# Faceb.net
KiCad netlist of a schematic drawn in EAGLE
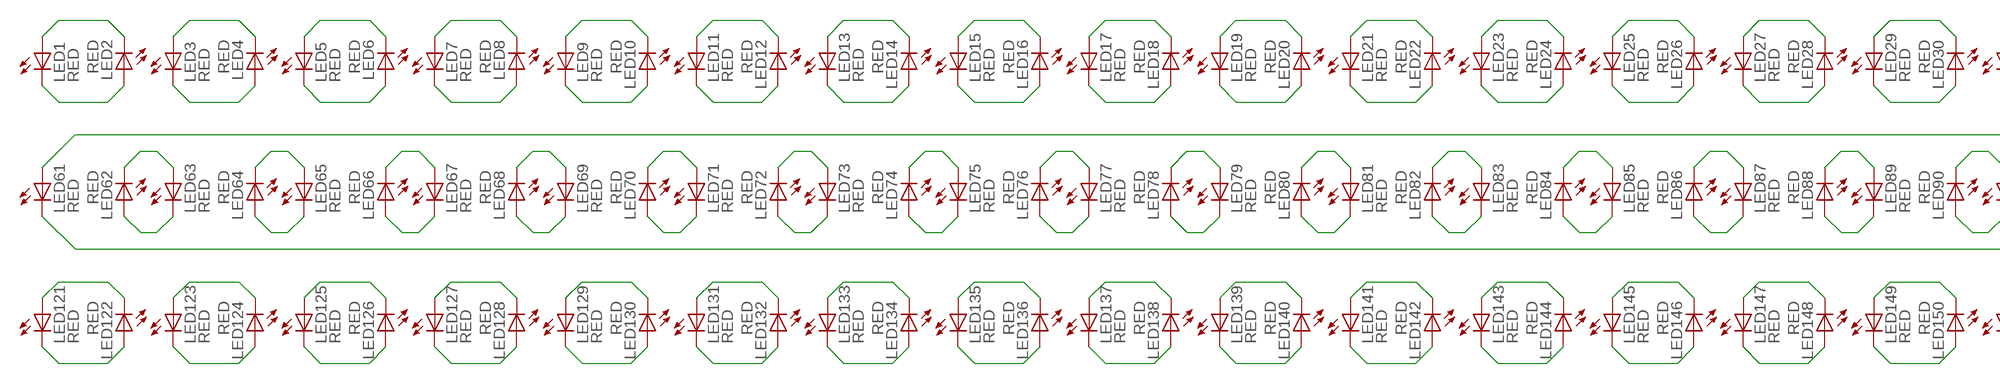
[diagram p0: schematic, sheet 1, part 1 of 2]
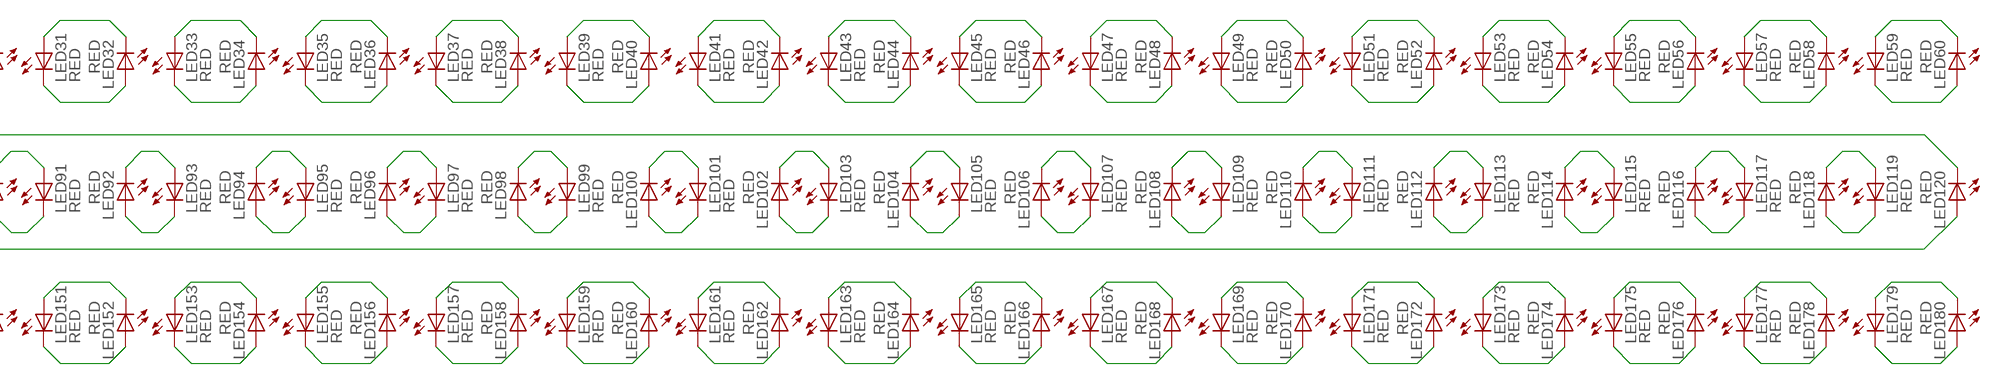
[diagram p1: schematic, sheet 1, part 2 of 2]

(export (version "E")
  (design (tool "Eeschema 10.0.6"))
  (components
    (comp (ref "LED1")
      (value "RED")
      (footprint "eagle-import:LED-0603")
      (libsource (lib "eagle-import") (part "LED0603"))
    )
    (comp (ref "LED2")
      (value "RED")
      (footprint "eagle-import:LED-0603")
      (libsource (lib "eagle-import") (part "LED0603"))
    )
    (comp (ref "LED3")
      (value "RED")
      (footprint "eagle-import:LED-0603")
      (libsource (lib "eagle-import") (part "LED0603"))
    )
    (comp (ref "LED4")
      (value "RED")
      (footprint "eagle-import:LED-0603")
      (libsource (lib "eagle-import") (part "LED0603"))
    )
    (comp (ref "LED5")
      (value "RED")
      (footprint "eagle-import:LED-0603")
      (libsource (lib "eagle-import") (part "LED0603"))
    )
    (comp (ref "LED6")
      (value "RED")
      (footprint "eagle-import:LED-0603")
      (libsource (lib "eagle-import") (part "LED0603"))
    )
    (comp (ref "LED7")
      (value "RED")
      (footprint "eagle-import:LED-0603")
      (libsource (lib "eagle-import") (part "LED0603"))
    )
    (comp (ref "LED8")
      (value "RED")
      (footprint "eagle-import:LED-0603")
      (libsource (lib "eagle-import") (part "LED0603"))
    )
    (comp (ref "LED9")
      (value "RED")
      (footprint "eagle-import:LED-0603")
      (libsource (lib "eagle-import") (part "LED0603"))
    )
    (comp (ref "LED10")
      (value "RED")
      (footprint "eagle-import:LED-0603")
      (libsource (lib "eagle-import") (part "LED0603"))
    )
    (comp (ref "LED11")
      (value "RED")
      (footprint "eagle-import:LED-0603")
      (libsource (lib "eagle-import") (part "LED0603"))
    )
    (comp (ref "LED12")
      (value "RED")
      (footprint "eagle-import:LED-0603")
      (libsource (lib "eagle-import") (part "LED0603"))
    )
    (comp (ref "LED13")
      (value "RED")
      (footprint "eagle-import:LED-0603")
      (libsource (lib "eagle-import") (part "LED0603"))
    )
    (comp (ref "LED14")
      (value "RED")
      (footprint "eagle-import:LED-0603")
      (libsource (lib "eagle-import") (part "LED0603"))
    )
    (comp (ref "LED15")
      (value "RED")
      (footprint "eagle-import:LED-0603")
      (libsource (lib "eagle-import") (part "LED0603"))
    )
    (comp (ref "LED16")
      (value "RED")
      (footprint "eagle-import:LED-0603")
      (libsource (lib "eagle-import") (part "LED0603"))
    )
    (comp (ref "LED17")
      (value "RED")
      (footprint "eagle-import:LED-0603")
      (libsource (lib "eagle-import") (part "LED0603"))
    )
    (comp (ref "LED18")
      (value "RED")
      (footprint "eagle-import:LED-0603")
      (libsource (lib "eagle-import") (part "LED0603"))
    )
    (comp (ref "LED19")
      (value "RED")
      (footprint "eagle-import:LED-0603")
      (libsource (lib "eagle-import") (part "LED0603"))
    )
    (comp (ref "LED20")
      (value "RED")
      (footprint "eagle-import:LED-0603")
      (libsource (lib "eagle-import") (part "LED0603"))
    )
    (comp (ref "LED21")
      (value "RED")
      (footprint "eagle-import:LED-0603")
      (libsource (lib "eagle-import") (part "LED0603"))
    )
    (comp (ref "LED22")
      (value "RED")
      (footprint "eagle-import:LED-0603")
      (libsource (lib "eagle-import") (part "LED0603"))
    )
    (comp (ref "LED23")
      (value "RED")
      (footprint "eagle-import:LED-0603")
      (libsource (lib "eagle-import") (part "LED0603"))
    )
    (comp (ref "LED24")
      (value "RED")
      (footprint "eagle-import:LED-0603")
      (libsource (lib "eagle-import") (part "LED0603"))
    )
    (comp (ref "LED25")
      (value "RED")
      (footprint "eagle-import:LED-0603")
      (libsource (lib "eagle-import") (part "LED0603"))
    )
    (comp (ref "LED26")
      (value "RED")
      (footprint "eagle-import:LED-0603")
      (libsource (lib "eagle-import") (part "LED0603"))
    )
    (comp (ref "LED27")
      (value "RED")
      (footprint "eagle-import:LED-0603")
      (libsource (lib "eagle-import") (part "LED0603"))
    )
    (comp (ref "LED28")
      (value "RED")
      (footprint "eagle-import:LED-0603")
      (libsource (lib "eagle-import") (part "LED0603"))
    )
    (comp (ref "LED29")
      (value "RED")
      (footprint "eagle-import:LED-0603")
      (libsource (lib "eagle-import") (part "LED0603"))
    )
    (comp (ref "LED30")
      (value "RED")
      (footprint "eagle-import:LED-0603")
      (libsource (lib "eagle-import") (part "LED0603"))
    )
    (comp (ref "LED31")
      (value "RED")
      (footprint "eagle-import:LED-0603")
      (libsource (lib "eagle-import") (part "LED0603"))
    )
    (comp (ref "LED32")
      (value "RED")
      (footprint "eagle-import:LED-0603")
      (libsource (lib "eagle-import") (part "LED0603"))
    )
    (comp (ref "LED33")
      (value "RED")
      (footprint "eagle-import:LED-0603")
      (libsource (lib "eagle-import") (part "LED0603"))
    )
    (comp (ref "LED34")
      (value "RED")
      (footprint "eagle-import:LED-0603")
      (libsource (lib "eagle-import") (part "LED0603"))
    )
    (comp (ref "LED35")
      (value "RED")
      (footprint "eagle-import:LED-0603")
      (libsource (lib "eagle-import") (part "LED0603"))
    )
    (comp (ref "LED36")
      (value "RED")
      (footprint "eagle-import:LED-0603")
      (libsource (lib "eagle-import") (part "LED0603"))
    )
    (comp (ref "LED37")
      (value "RED")
      (footprint "eagle-import:LED-0603")
      (libsource (lib "eagle-import") (part "LED0603"))
    )
    (comp (ref "LED38")
      (value "RED")
      (footprint "eagle-import:LED-0603")
      (libsource (lib "eagle-import") (part "LED0603"))
    )
    (comp (ref "LED39")
      (value "RED")
      (footprint "eagle-import:LED-0603")
      (libsource (lib "eagle-import") (part "LED0603"))
    )
    (comp (ref "LED40")
      (value "RED")
      (footprint "eagle-import:LED-0603")
      (libsource (lib "eagle-import") (part "LED0603"))
    )
    (comp (ref "LED41")
      (value "RED")
      (footprint "eagle-import:LED-0603")
      (libsource (lib "eagle-import") (part "LED0603"))
    )
    (comp (ref "LED42")
      (value "RED")
      (footprint "eagle-import:LED-0603")
      (libsource (lib "eagle-import") (part "LED0603"))
    )
    (comp (ref "LED43")
      (value "RED")
      (footprint "eagle-import:LED-0603")
      (libsource (lib "eagle-import") (part "LED0603"))
    )
    (comp (ref "LED44")
      (value "RED")
      (footprint "eagle-import:LED-0603")
      (libsource (lib "eagle-import") (part "LED0603"))
    )
    (comp (ref "LED45")
      (value "RED")
      (footprint "eagle-import:LED-0603")
      (libsource (lib "eagle-import") (part "LED0603"))
    )
    (comp (ref "LED46")
      (value "RED")
      (footprint "eagle-import:LED-0603")
      (libsource (lib "eagle-import") (part "LED0603"))
    )
    (comp (ref "LED47")
      (value "RED")
      (footprint "eagle-import:LED-0603")
      (libsource (lib "eagle-import") (part "LED0603"))
    )
    (comp (ref "LED48")
      (value "RED")
      (footprint "eagle-import:LED-0603")
      (libsource (lib "eagle-import") (part "LED0603"))
    )
    (comp (ref "LED49")
      (value "RED")
      (footprint "eagle-import:LED-0603")
      (libsource (lib "eagle-import") (part "LED0603"))
    )
    (comp (ref "LED50")
      (value "RED")
      (footprint "eagle-import:LED-0603")
      (libsource (lib "eagle-import") (part "LED0603"))
    )
    (comp (ref "LED51")
      (value "RED")
      (footprint "eagle-import:LED-0603")
      (libsource (lib "eagle-import") (part "LED0603"))
    )
    (comp (ref "LED52")
      (value "RED")
      (footprint "eagle-import:LED-0603")
      (libsource (lib "eagle-import") (part "LED0603"))
    )
    (comp (ref "LED53")
      (value "RED")
      (footprint "eagle-import:LED-0603")
      (libsource (lib "eagle-import") (part "LED0603"))
    )
    (comp (ref "LED54")
      (value "RED")
      (footprint "eagle-import:LED-0603")
      (libsource (lib "eagle-import") (part "LED0603"))
    )
    (comp (ref "LED55")
      (value "RED")
      (footprint "eagle-import:LED-0603")
      (libsource (lib "eagle-import") (part "LED0603"))
    )
    (comp (ref "LED56")
      (value "RED")
      (footprint "eagle-import:LED-0603")
      (libsource (lib "eagle-import") (part "LED0603"))
    )
    (comp (ref "LED57")
      (value "RED")
      (footprint "eagle-import:LED-0603")
      (libsource (lib "eagle-import") (part "LED0603"))
    )
    (comp (ref "LED58")
      (value "RED")
      (footprint "eagle-import:LED-0603")
      (libsource (lib "eagle-import") (part "LED0603"))
    )
    (comp (ref "LED59")
      (value "RED")
      (footprint "eagle-import:LED-0603")
      (libsource (lib "eagle-import") (part "LED0603"))
    )
    (comp (ref "LED60")
      (value "RED")
      (footprint "eagle-import:LED-0603")
      (libsource (lib "eagle-import") (part "LED0603"))
    )
    (comp (ref "LED61")
      (value "RED")
      (footprint "eagle-import:LED-0603")
      (libsource (lib "eagle-import") (part "LED0603"))
    )
    (comp (ref "LED62")
      (value "RED")
      (footprint "eagle-import:LED-0603")
      (libsource (lib "eagle-import") (part "LED0603"))
    )
    (comp (ref "LED63")
      (value "RED")
      (footprint "eagle-import:LED-0603")
      (libsource (lib "eagle-import") (part "LED0603"))
    )
    (comp (ref "LED64")
      (value "RED")
      (footprint "eagle-import:LED-0603")
      (libsource (lib "eagle-import") (part "LED0603"))
    )
    (comp (ref "LED65")
      (value "RED")
      (footprint "eagle-import:LED-0603")
      (libsource (lib "eagle-import") (part "LED0603"))
    )
    (comp (ref "LED66")
      (value "RED")
      (footprint "eagle-import:LED-0603")
      (libsource (lib "eagle-import") (part "LED0603"))
    )
    (comp (ref "LED67")
      (value "RED")
      (footprint "eagle-import:LED-0603")
      (libsource (lib "eagle-import") (part "LED0603"))
    )
    (comp (ref "LED68")
      (value "RED")
      (footprint "eagle-import:LED-0603")
      (libsource (lib "eagle-import") (part "LED0603"))
    )
    (comp (ref "LED69")
      (value "RED")
      (footprint "eagle-import:LED-0603")
      (libsource (lib "eagle-import") (part "LED0603"))
    )
    (comp (ref "LED70")
      (value "RED")
      (footprint "eagle-import:LED-0603")
      (libsource (lib "eagle-import") (part "LED0603"))
    )
    (comp (ref "LED71")
      (value "RED")
      (footprint "eagle-import:LED-0603")
      (libsource (lib "eagle-import") (part "LED0603"))
    )
    (comp (ref "LED72")
      (value "RED")
      (footprint "eagle-import:LED-0603")
      (libsource (lib "eagle-import") (part "LED0603"))
    )
    (comp (ref "LED73")
      (value "RED")
      (footprint "eagle-import:LED-0603")
      (libsource (lib "eagle-import") (part "LED0603"))
    )
    (comp (ref "LED74")
      (value "RED")
      (footprint "eagle-import:LED-0603")
      (libsource (lib "eagle-import") (part "LED0603"))
    )
    (comp (ref "LED75")
      (value "RED")
      (footprint "eagle-import:LED-0603")
      (libsource (lib "eagle-import") (part "LED0603"))
    )
    (comp (ref "LED76")
      (value "RED")
      (footprint "eagle-import:LED-0603")
      (libsource (lib "eagle-import") (part "LED0603"))
    )
    (comp (ref "LED77")
      (value "RED")
      (footprint "eagle-import:LED-0603")
      (libsource (lib "eagle-import") (part "LED0603"))
    )
    (comp (ref "LED78")
      (value "RED")
      (footprint "eagle-import:LED-0603")
      (libsource (lib "eagle-import") (part "LED0603"))
    )
    (comp (ref "LED79")
      (value "RED")
      (footprint "eagle-import:LED-0603")
      (libsource (lib "eagle-import") (part "LED0603"))
    )
    (comp (ref "LED80")
      (value "RED")
      (footprint "eagle-import:LED-0603")
      (libsource (lib "eagle-import") (part "LED0603"))
    )
    (comp (ref "LED81")
      (value "RED")
      (footprint "eagle-import:LED-0603")
      (libsource (lib "eagle-import") (part "LED0603"))
    )
    (comp (ref "LED82")
      (value "RED")
      (footprint "eagle-import:LED-0603")
      (libsource (lib "eagle-import") (part "LED0603"))
    )
    (comp (ref "LED83")
      (value "RED")
      (footprint "eagle-import:LED-0603")
      (libsource (lib "eagle-import") (part "LED0603"))
    )
    (comp (ref "LED84")
      (value "RED")
      (footprint "eagle-import:LED-0603")
      (libsource (lib "eagle-import") (part "LED0603"))
    )
    (comp (ref "LED85")
      (value "RED")
      (footprint "eagle-import:LED-0603")
      (libsource (lib "eagle-import") (part "LED0603"))
    )
    (comp (ref "LED86")
      (value "RED")
      (footprint "eagle-import:LED-0603")
      (libsource (lib "eagle-import") (part "LED0603"))
    )
    (comp (ref "LED87")
      (value "RED")
      (footprint "eagle-import:LED-0603")
      (libsource (lib "eagle-import") (part "LED0603"))
    )
    (comp (ref "LED88")
      (value "RED")
      (footprint "eagle-import:LED-0603")
      (libsource (lib "eagle-import") (part "LED0603"))
    )
    (comp (ref "LED89")
      (value "RED")
      (footprint "eagle-import:LED-0603")
      (libsource (lib "eagle-import") (part "LED0603"))
    )
    (comp (ref "LED90")
      (value "RED")
      (footprint "eagle-import:LED-0603")
      (libsource (lib "eagle-import") (part "LED0603"))
    )
    (comp (ref "LED91")
      (value "RED")
      (footprint "eagle-import:LED-0603")
      (libsource (lib "eagle-import") (part "LED0603"))
    )
    (comp (ref "LED92")
      (value "RED")
      (footprint "eagle-import:LED-0603")
      (libsource (lib "eagle-import") (part "LED0603"))
    )
    (comp (ref "LED93")
      (value "RED")
      (footprint "eagle-import:LED-0603")
      (libsource (lib "eagle-import") (part "LED0603"))
    )
    (comp (ref "LED94")
      (value "RED")
      (footprint "eagle-import:LED-0603")
      (libsource (lib "eagle-import") (part "LED0603"))
    )
    (comp (ref "LED95")
      (value "RED")
      (footprint "eagle-import:LED-0603")
      (libsource (lib "eagle-import") (part "LED0603"))
    )
    (comp (ref "LED96")
      (value "RED")
      (footprint "eagle-import:LED-0603")
      (libsource (lib "eagle-import") (part "LED0603"))
    )
    (comp (ref "LED97")
      (value "RED")
      (footprint "eagle-import:LED-0603")
      (libsource (lib "eagle-import") (part "LED0603"))
    )
    (comp (ref "LED98")
      (value "RED")
      (footprint "eagle-import:LED-0603")
      (libsource (lib "eagle-import") (part "LED0603"))
    )
    (comp (ref "LED99")
      (value "RED")
      (footprint "eagle-import:LED-0603")
      (libsource (lib "eagle-import") (part "LED0603"))
    )
    (comp (ref "LED100")
      (value "RED")
      (footprint "eagle-import:LED-0603")
      (libsource (lib "eagle-import") (part "LED0603"))
    )
    (comp (ref "LED101")
      (value "RED")
      (footprint "eagle-import:LED-0603")
      (libsource (lib "eagle-import") (part "LED0603"))
    )
    (comp (ref "LED102")
      (value "RED")
      (footprint "eagle-import:LED-0603")
      (libsource (lib "eagle-import") (part "LED0603"))
    )
    (comp (ref "LED103")
      (value "RED")
      (footprint "eagle-import:LED-0603")
      (libsource (lib "eagle-import") (part "LED0603"))
    )
    (comp (ref "LED104")
      (value "RED")
      (footprint "eagle-import:LED-0603")
      (libsource (lib "eagle-import") (part "LED0603"))
    )
    (comp (ref "LED105")
      (value "RED")
      (footprint "eagle-import:LED-0603")
      (libsource (lib "eagle-import") (part "LED0603"))
    )
    (comp (ref "LED106")
      (value "RED")
      (footprint "eagle-import:LED-0603")
      (libsource (lib "eagle-import") (part "LED0603"))
    )
    (comp (ref "LED107")
      (value "RED")
      (footprint "eagle-import:LED-0603")
      (libsource (lib "eagle-import") (part "LED0603"))
    )
    (comp (ref "LED108")
      (value "RED")
      (footprint "eagle-import:LED-0603")
      (libsource (lib "eagle-import") (part "LED0603"))
    )
    (comp (ref "LED109")
      (value "RED")
      (footprint "eagle-import:LED-0603")
      (libsource (lib "eagle-import") (part "LED0603"))
    )
    (comp (ref "LED110")
      (value "RED")
      (footprint "eagle-import:LED-0603")
      (libsource (lib "eagle-import") (part "LED0603"))
    )
    (comp (ref "LED111")
      (value "RED")
      (footprint "eagle-import:LED-0603")
      (libsource (lib "eagle-import") (part "LED0603"))
    )
    (comp (ref "LED112")
      (value "RED")
      (footprint "eagle-import:LED-0603")
      (libsource (lib "eagle-import") (part "LED0603"))
    )
    (comp (ref "LED113")
      (value "RED")
      (footprint "eagle-import:LED-0603")
      (libsource (lib "eagle-import") (part "LED0603"))
    )
    (comp (ref "LED114")
      (value "RED")
      (footprint "eagle-import:LED-0603")
      (libsource (lib "eagle-import") (part "LED0603"))
    )
    (comp (ref "LED115")
      (value "RED")
      (footprint "eagle-import:LED-0603")
      (libsource (lib "eagle-import") (part "LED0603"))
    )
    (comp (ref "LED116")
      (value "RED")
      (footprint "eagle-import:LED-0603")
      (libsource (lib "eagle-import") (part "LED0603"))
    )
    (comp (ref "LED117")
      (value "RED")
      (footprint "eagle-import:LED-0603")
      (libsource (lib "eagle-import") (part "LED0603"))
    )
    (comp (ref "LED118")
      (value "RED")
      (footprint "eagle-import:LED-0603")
      (libsource (lib "eagle-import") (part "LED0603"))
    )
    (comp (ref "LED119")
      (value "RED")
      (footprint "eagle-import:LED-0603")
      (libsource (lib "eagle-import") (part "LED0603"))
    )
    (comp (ref "LED120")
      (value "RED")
      (footprint "eagle-import:LED-0603")
      (libsource (lib "eagle-import") (part "LED0603"))
    )
    (comp (ref "LED121")
      (value "RED")
      (footprint "eagle-import:LED-0603")
      (libsource (lib "eagle-import") (part "LED0603"))
    )
    (comp (ref "LED122")
      (value "RED")
      (footprint "eagle-import:LED-0603")
      (libsource (lib "eagle-import") (part "LED0603"))
    )
    (comp (ref "LED123")
      (value "RED")
      (footprint "eagle-import:LED-0603")
      (libsource (lib "eagle-import") (part "LED0603"))
    )
    (comp (ref "LED124")
      (value "RED")
      (footprint "eagle-import:LED-0603")
      (libsource (lib "eagle-import") (part "LED0603"))
    )
    (comp (ref "LED125")
      (value "RED")
      (footprint "eagle-import:LED-0603")
      (libsource (lib "eagle-import") (part "LED0603"))
    )
    (comp (ref "LED126")
      (value "RED")
      (footprint "eagle-import:LED-0603")
      (libsource (lib "eagle-import") (part "LED0603"))
    )
    (comp (ref "LED127")
      (value "RED")
      (footprint "eagle-import:LED-0603")
      (libsource (lib "eagle-import") (part "LED0603"))
    )
    (comp (ref "LED128")
      (value "RED")
      (footprint "eagle-import:LED-0603")
      (libsource (lib "eagle-import") (part "LED0603"))
    )
    (comp (ref "LED129")
      (value "RED")
      (footprint "eagle-import:LED-0603")
      (libsource (lib "eagle-import") (part "LED0603"))
    )
    (comp (ref "LED130")
      (value "RED")
      (footprint "eagle-import:LED-0603")
      (libsource (lib "eagle-import") (part "LED0603"))
    )
    (comp (ref "LED131")
      (value "RED")
      (footprint "eagle-import:LED-0603")
      (libsource (lib "eagle-import") (part "LED0603"))
    )
    (comp (ref "LED132")
      (value "RED")
      (footprint "eagle-import:LED-0603")
      (libsource (lib "eagle-import") (part "LED0603"))
    )
    (comp (ref "LED133")
      (value "RED")
      (footprint "eagle-import:LED-0603")
      (libsource (lib "eagle-import") (part "LED0603"))
    )
    (comp (ref "LED134")
      (value "RED")
      (footprint "eagle-import:LED-0603")
      (libsource (lib "eagle-import") (part "LED0603"))
    )
    (comp (ref "LED135")
      (value "RED")
      (footprint "eagle-import:LED-0603")
      (libsource (lib "eagle-import") (part "LED0603"))
    )
    (comp (ref "LED136")
      (value "RED")
      (footprint "eagle-import:LED-0603")
      (libsource (lib "eagle-import") (part "LED0603"))
    )
    (comp (ref "LED137")
      (value "RED")
      (footprint "eagle-import:LED-0603")
      (libsource (lib "eagle-import") (part "LED0603"))
    )
    (comp (ref "LED138")
      (value "RED")
      (footprint "eagle-import:LED-0603")
      (libsource (lib "eagle-import") (part "LED0603"))
    )
    (comp (ref "LED139")
      (value "RED")
      (footprint "eagle-import:LED-0603")
      (libsource (lib "eagle-import") (part "LED0603"))
    )
    (comp (ref "LED140")
      (value "RED")
      (footprint "eagle-import:LED-0603")
      (libsource (lib "eagle-import") (part "LED0603"))
    )
    (comp (ref "LED141")
      (value "RED")
      (footprint "eagle-import:LED-0603")
      (libsource (lib "eagle-import") (part "LED0603"))
    )
    (comp (ref "LED142")
      (value "RED")
      (footprint "eagle-import:LED-0603")
      (libsource (lib "eagle-import") (part "LED0603"))
    )
    (comp (ref "LED143")
      (value "RED")
      (footprint "eagle-import:LED-0603")
      (libsource (lib "eagle-import") (part "LED0603"))
    )
    (comp (ref "LED144")
      (value "RED")
      (footprint "eagle-import:LED-0603")
      (libsource (lib "eagle-import") (part "LED0603"))
    )
    (comp (ref "LED145")
      (value "RED")
      (footprint "eagle-import:LED-0603")
      (libsource (lib "eagle-import") (part "LED0603"))
    )
    (comp (ref "LED146")
      (value "RED")
      (footprint "eagle-import:LED-0603")
      (libsource (lib "eagle-import") (part "LED0603"))
    )
    (comp (ref "LED147")
      (value "RED")
      (footprint "eagle-import:LED-0603")
      (libsource (lib "eagle-import") (part "LED0603"))
    )
    (comp (ref "LED148")
      (value "RED")
      (footprint "eagle-import:LED-0603")
      (libsource (lib "eagle-import") (part "LED0603"))
    )
    (comp (ref "LED149")
      (value "RED")
      (footprint "eagle-import:LED-0603")
      (libsource (lib "eagle-import") (part "LED0603"))
    )
    (comp (ref "LED150")
      (value "RED")
      (footprint "eagle-import:LED-0603")
      (libsource (lib "eagle-import") (part "LED0603"))
    )
    (comp (ref "LED151")
      (value "RED")
      (footprint "eagle-import:LED-0603")
      (libsource (lib "eagle-import") (part "LED0603"))
    )
    (comp (ref "LED152")
      (value "RED")
      (footprint "eagle-import:LED-0603")
      (libsource (lib "eagle-import") (part "LED0603"))
    )
    (comp (ref "LED153")
      (value "RED")
      (footprint "eagle-import:LED-0603")
      (libsource (lib "eagle-import") (part "LED0603"))
    )
    (comp (ref "LED154")
      (value "RED")
      (footprint "eagle-import:LED-0603")
      (libsource (lib "eagle-import") (part "LED0603"))
    )
    (comp (ref "LED155")
      (value "RED")
      (footprint "eagle-import:LED-0603")
      (libsource (lib "eagle-import") (part "LED0603"))
    )
    (comp (ref "LED156")
      (value "RED")
      (footprint "eagle-import:LED-0603")
      (libsource (lib "eagle-import") (part "LED0603"))
    )
    (comp (ref "LED157")
      (value "RED")
      (footprint "eagle-import:LED-0603")
      (libsource (lib "eagle-import") (part "LED0603"))
    )
    (comp (ref "LED158")
      (value "RED")
      (footprint "eagle-import:LED-0603")
      (libsource (lib "eagle-import") (part "LED0603"))
    )
    (comp (ref "LED159")
      (value "RED")
      (footprint "eagle-import:LED-0603")
      (libsource (lib "eagle-import") (part "LED0603"))
    )
    (comp (ref "LED160")
      (value "RED")
      (footprint "eagle-import:LED-0603")
      (libsource (lib "eagle-import") (part "LED0603"))
    )
    (comp (ref "LED161")
      (value "RED")
      (footprint "eagle-import:LED-0603")
      (libsource (lib "eagle-import") (part "LED0603"))
    )
    (comp (ref "LED162")
      (value "RED")
      (footprint "eagle-import:LED-0603")
      (libsource (lib "eagle-import") (part "LED0603"))
    )
    (comp (ref "LED163")
      (value "RED")
      (footprint "eagle-import:LED-0603")
      (libsource (lib "eagle-import") (part "LED0603"))
    )
    (comp (ref "LED164")
      (value "RED")
      (footprint "eagle-import:LED-0603")
      (libsource (lib "eagle-import") (part "LED0603"))
    )
    (comp (ref "LED165")
      (value "RED")
      (footprint "eagle-import:LED-0603")
      (libsource (lib "eagle-import") (part "LED0603"))
    )
    (comp (ref "LED166")
      (value "RED")
      (footprint "eagle-import:LED-0603")
      (libsource (lib "eagle-import") (part "LED0603"))
    )
    (comp (ref "LED167")
      (value "RED")
      (footprint "eagle-import:LED-0603")
      (libsource (lib "eagle-import") (part "LED0603"))
    )
    (comp (ref "LED168")
      (value "RED")
      (footprint "eagle-import:LED-0603")
      (libsource (lib "eagle-import") (part "LED0603"))
    )
    (comp (ref "LED169")
      (value "RED")
      (footprint "eagle-import:LED-0603")
      (libsource (lib "eagle-import") (part "LED0603"))
    )
    (comp (ref "LED170")
      (value "RED")
      (footprint "eagle-import:LED-0603")
      (libsource (lib "eagle-import") (part "LED0603"))
    )
    (comp (ref "LED171")
      (value "RED")
      (footprint "eagle-import:LED-0603")
      (libsource (lib "eagle-import") (part "LED0603"))
    )
    (comp (ref "LED172")
      (value "RED")
      (footprint "eagle-import:LED-0603")
      (libsource (lib "eagle-import") (part "LED0603"))
    )
    (comp (ref "LED173")
      (value "RED")
      (footprint "eagle-import:LED-0603")
      (libsource (lib "eagle-import") (part "LED0603"))
    )
    (comp (ref "LED174")
      (value "RED")
      (footprint "eagle-import:LED-0603")
      (libsource (lib "eagle-import") (part "LED0603"))
    )
    (comp (ref "LED175")
      (value "RED")
      (footprint "eagle-import:LED-0603")
      (libsource (lib "eagle-import") (part "LED0603"))
    )
    (comp (ref "LED176")
      (value "RED")
      (footprint "eagle-import:LED-0603")
      (libsource (lib "eagle-import") (part "LED0603"))
    )
    (comp (ref "LED177")
      (value "RED")
      (footprint "eagle-import:LED-0603")
      (libsource (lib "eagle-import") (part "LED0603"))
    )
    (comp (ref "LED178")
      (value "RED")
      (footprint "eagle-import:LED-0603")
      (libsource (lib "eagle-import") (part "LED0603"))
    )
    (comp (ref "LED179")
      (value "RED")
      (footprint "eagle-import:LED-0603")
      (libsource (lib "eagle-import") (part "LED0603"))
    )
    (comp (ref "LED180")
      (value "RED")
      (footprint "eagle-import:LED-0603")
      (libsource (lib "eagle-import") (part "LED0603"))
    )
  )
  (nets
    (net (code "1") (name "Net-(LED1-PadA)") (class "Default")
      (node (ref "LED1") (pin "A") (pinfunction "A_A") (pintype "passive"))
      (node (ref "LED2") (pin "C") (pinfunction "C_C") (pintype "passive"))
    )
    (net (code "2") (name "Net-(LED1-PadC)") (class "Default")
      (node (ref "LED1") (pin "C") (pinfunction "C_C") (pintype "passive"))
      (node (ref "LED2") (pin "A") (pinfunction "A_A") (pintype "passive"))
    )
    (net (code "3") (name "Net-(LED3-PadA)") (class "Default")
      (node (ref "LED3") (pin "A") (pinfunction "A_A") (pintype "passive"))
      (node (ref "LED4") (pin "C") (pinfunction "C_C") (pintype "passive"))
    )
    (net (code "4") (name "Net-(LED3-PadC)") (class "Default")
      (node (ref "LED3") (pin "C") (pinfunction "C_C") (pintype "passive"))
      (node (ref "LED4") (pin "A") (pinfunction "A_A") (pintype "passive"))
    )
    (net (code "5") (name "Net-(LED5-PadA)") (class "Default")
      (node (ref "LED5") (pin "A") (pinfunction "A_A") (pintype "passive"))
      (node (ref "LED6") (pin "C") (pinfunction "C_C") (pintype "passive"))
    )
    (net (code "6") (name "Net-(LED5-PadC)") (class "Default")
      (node (ref "LED5") (pin "C") (pinfunction "C_C") (pintype "passive"))
      (node (ref "LED6") (pin "A") (pinfunction "A_A") (pintype "passive"))
    )
    (net (code "7") (name "Net-(LED7-PadA)") (class "Default")
      (node (ref "LED7") (pin "A") (pinfunction "A_A") (pintype "passive"))
      (node (ref "LED8") (pin "C") (pinfunction "C_C") (pintype "passive"))
    )
    (net (code "8") (name "Net-(LED7-PadC)") (class "Default")
      (node (ref "LED7") (pin "C") (pinfunction "C_C") (pintype "passive"))
      (node (ref "LED8") (pin "A") (pinfunction "A_A") (pintype "passive"))
    )
    (net (code "9") (name "Net-(LED10-PadA)") (class "Default")
      (node (ref "LED10") (pin "A") (pinfunction "A_A") (pintype "passive"))
      (node (ref "LED9") (pin "C") (pinfunction "C_C") (pintype "passive"))
    )
    (net (code "10") (name "Net-(LED10-PadC)") (class "Default")
      (node (ref "LED10") (pin "C") (pinfunction "C_C") (pintype "passive"))
      (node (ref "LED9") (pin "A") (pinfunction "A_A") (pintype "passive"))
    )
    (net (code "11") (name "Net-(LED11-PadA)") (class "Default")
      (node (ref "LED11") (pin "A") (pinfunction "A_A") (pintype "passive"))
      (node (ref "LED12") (pin "C") (pinfunction "C_C") (pintype "passive"))
    )
    (net (code "12") (name "Net-(LED11-PadC)") (class "Default")
      (node (ref "LED11") (pin "C") (pinfunction "C_C") (pintype "passive"))
      (node (ref "LED12") (pin "A") (pinfunction "A_A") (pintype "passive"))
    )
    (net (code "13") (name "Net-(LED13-PadA)") (class "Default")
      (node (ref "LED13") (pin "A") (pinfunction "A_A") (pintype "passive"))
      (node (ref "LED14") (pin "C") (pinfunction "C_C") (pintype "passive"))
    )
    (net (code "14") (name "Net-(LED13-PadC)") (class "Default")
      (node (ref "LED13") (pin "C") (pinfunction "C_C") (pintype "passive"))
      (node (ref "LED14") (pin "A") (pinfunction "A_A") (pintype "passive"))
    )
    (net (code "15") (name "Net-(LED15-PadA)") (class "Default")
      (node (ref "LED15") (pin "A") (pinfunction "A_A") (pintype "passive"))
      (node (ref "LED16") (pin "C") (pinfunction "C_C") (pintype "passive"))
    )
    (net (code "16") (name "Net-(LED15-PadC)") (class "Default")
      (node (ref "LED15") (pin "C") (pinfunction "C_C") (pintype "passive"))
      (node (ref "LED16") (pin "A") (pinfunction "A_A") (pintype "passive"))
    )
    (net (code "17") (name "Net-(LED17-PadA)") (class "Default")
      (node (ref "LED17") (pin "A") (pinfunction "A_A") (pintype "passive"))
      (node (ref "LED18") (pin "C") (pinfunction "C_C") (pintype "passive"))
    )
    (net (code "18") (name "Net-(LED17-PadC)") (class "Default")
      (node (ref "LED17") (pin "C") (pinfunction "C_C") (pintype "passive"))
      (node (ref "LED18") (pin "A") (pinfunction "A_A") (pintype "passive"))
    )
    (net (code "19") (name "Net-(LED19-PadA)") (class "Default")
      (node (ref "LED19") (pin "A") (pinfunction "A_A") (pintype "passive"))
      (node (ref "LED20") (pin "C") (pinfunction "C_C") (pintype "passive"))
    )
    (net (code "20") (name "Net-(LED19-PadC)") (class "Default")
      (node (ref "LED19") (pin "C") (pinfunction "C_C") (pintype "passive"))
      (node (ref "LED20") (pin "A") (pinfunction "A_A") (pintype "passive"))
    )
    (net (code "21") (name "Net-(LED21-PadA)") (class "Default")
      (node (ref "LED21") (pin "A") (pinfunction "A_A") (pintype "passive"))
      (node (ref "LED22") (pin "C") (pinfunction "C_C") (pintype "passive"))
    )
    (net (code "22") (name "Net-(LED21-PadC)") (class "Default")
      (node (ref "LED21") (pin "C") (pinfunction "C_C") (pintype "passive"))
      (node (ref "LED22") (pin "A") (pinfunction "A_A") (pintype "passive"))
    )
    (net (code "23") (name "Net-(LED23-PadA)") (class "Default")
      (node (ref "LED23") (pin "A") (pinfunction "A_A") (pintype "passive"))
      (node (ref "LED24") (pin "C") (pinfunction "C_C") (pintype "passive"))
    )
    (net (code "24") (name "Net-(LED23-PadC)") (class "Default")
      (node (ref "LED23") (pin "C") (pinfunction "C_C") (pintype "passive"))
      (node (ref "LED24") (pin "A") (pinfunction "A_A") (pintype "passive"))
    )
    (net (code "25") (name "Net-(LED25-PadA)") (class "Default")
      (node (ref "LED25") (pin "A") (pinfunction "A_A") (pintype "passive"))
      (node (ref "LED26") (pin "C") (pinfunction "C_C") (pintype "passive"))
    )
    (net (code "26") (name "Net-(LED25-PadC)") (class "Default")
      (node (ref "LED25") (pin "C") (pinfunction "C_C") (pintype "passive"))
      (node (ref "LED26") (pin "A") (pinfunction "A_A") (pintype "passive"))
    )
    (net (code "27") (name "Net-(LED27-PadA)") (class "Default")
      (node (ref "LED27") (pin "A") (pinfunction "A_A") (pintype "passive"))
      (node (ref "LED28") (pin "C") (pinfunction "C_C") (pintype "passive"))
    )
    (net (code "28") (name "Net-(LED27-PadC)") (class "Default")
      (node (ref "LED27") (pin "C") (pinfunction "C_C") (pintype "passive"))
      (node (ref "LED28") (pin "A") (pinfunction "A_A") (pintype "passive"))
    )
    (net (code "29") (name "Net-(LED29-PadA)") (class "Default")
      (node (ref "LED29") (pin "A") (pinfunction "A_A") (pintype "passive"))
      (node (ref "LED30") (pin "C") (pinfunction "C_C") (pintype "passive"))
    )
    (net (code "30") (name "Net-(LED29-PadC)") (class "Default")
      (node (ref "LED29") (pin "C") (pinfunction "C_C") (pintype "passive"))
      (node (ref "LED30") (pin "A") (pinfunction "A_A") (pintype "passive"))
    )
    (net (code "31") (name "Net-(LED31-PadA)") (class "Default")
      (node (ref "LED31") (pin "A") (pinfunction "A_A") (pintype "passive"))
      (node (ref "LED32") (pin "C") (pinfunction "C_C") (pintype "passive"))
    )
    (net (code "32") (name "Net-(LED31-PadC)") (class "Default")
      (node (ref "LED31") (pin "C") (pinfunction "C_C") (pintype "passive"))
      (node (ref "LED32") (pin "A") (pinfunction "A_A") (pintype "passive"))
    )
    (net (code "33") (name "Net-(LED33-PadA)") (class "Default")
      (node (ref "LED33") (pin "A") (pinfunction "A_A") (pintype "passive"))
      (node (ref "LED34") (pin "C") (pinfunction "C_C") (pintype "passive"))
    )
    (net (code "34") (name "Net-(LED33-PadC)") (class "Default")
      (node (ref "LED33") (pin "C") (pinfunction "C_C") (pintype "passive"))
      (node (ref "LED34") (pin "A") (pinfunction "A_A") (pintype "passive"))
    )
    (net (code "35") (name "Net-(LED35-PadA)") (class "Default")
      (node (ref "LED35") (pin "A") (pinfunction "A_A") (pintype "passive"))
      (node (ref "LED36") (pin "C") (pinfunction "C_C") (pintype "passive"))
    )
    (net (code "36") (name "Net-(LED35-PadC)") (class "Default")
      (node (ref "LED35") (pin "C") (pinfunction "C_C") (pintype "passive"))
      (node (ref "LED36") (pin "A") (pinfunction "A_A") (pintype "passive"))
    )
    (net (code "37") (name "Net-(LED37-PadA)") (class "Default")
      (node (ref "LED37") (pin "A") (pinfunction "A_A") (pintype "passive"))
      (node (ref "LED38") (pin "C") (pinfunction "C_C") (pintype "passive"))
    )
    (net (code "38") (name "Net-(LED37-PadC)") (class "Default")
      (node (ref "LED37") (pin "C") (pinfunction "C_C") (pintype "passive"))
      (node (ref "LED38") (pin "A") (pinfunction "A_A") (pintype "passive"))
    )
    (net (code "39") (name "Net-(LED39-PadA)") (class "Default")
      (node (ref "LED39") (pin "A") (pinfunction "A_A") (pintype "passive"))
      (node (ref "LED40") (pin "C") (pinfunction "C_C") (pintype "passive"))
    )
    (net (code "40") (name "Net-(LED39-PadC)") (class "Default")
      (node (ref "LED39") (pin "C") (pinfunction "C_C") (pintype "passive"))
      (node (ref "LED40") (pin "A") (pinfunction "A_A") (pintype "passive"))
    )
    (net (code "41") (name "Net-(LED41-PadA)") (class "Default")
      (node (ref "LED41") (pin "A") (pinfunction "A_A") (pintype "passive"))
      (node (ref "LED42") (pin "C") (pinfunction "C_C") (pintype "passive"))
    )
    (net (code "42") (name "Net-(LED41-PadC)") (class "Default")
      (node (ref "LED41") (pin "C") (pinfunction "C_C") (pintype "passive"))
      (node (ref "LED42") (pin "A") (pinfunction "A_A") (pintype "passive"))
    )
    (net (code "43") (name "Net-(LED43-PadA)") (class "Default")
      (node (ref "LED43") (pin "A") (pinfunction "A_A") (pintype "passive"))
      (node (ref "LED44") (pin "C") (pinfunction "C_C") (pintype "passive"))
    )
    (net (code "44") (name "Net-(LED43-PadC)") (class "Default")
      (node (ref "LED43") (pin "C") (pinfunction "C_C") (pintype "passive"))
      (node (ref "LED44") (pin "A") (pinfunction "A_A") (pintype "passive"))
    )
    (net (code "45") (name "Net-(LED45-PadA)") (class "Default")
      (node (ref "LED45") (pin "A") (pinfunction "A_A") (pintype "passive"))
      (node (ref "LED46") (pin "C") (pinfunction "C_C") (pintype "passive"))
    )
    (net (code "46") (name "Net-(LED45-PadC)") (class "Default")
      (node (ref "LED45") (pin "C") (pinfunction "C_C") (pintype "passive"))
      (node (ref "LED46") (pin "A") (pinfunction "A_A") (pintype "passive"))
    )
    (net (code "47") (name "Net-(LED47-PadA)") (class "Default")
      (node (ref "LED47") (pin "A") (pinfunction "A_A") (pintype "passive"))
      (node (ref "LED48") (pin "C") (pinfunction "C_C") (pintype "passive"))
    )
    (net (code "48") (name "Net-(LED47-PadC)") (class "Default")
      (node (ref "LED47") (pin "C") (pinfunction "C_C") (pintype "passive"))
      (node (ref "LED48") (pin "A") (pinfunction "A_A") (pintype "passive"))
    )
    (net (code "49") (name "Net-(LED49-PadA)") (class "Default")
      (node (ref "LED49") (pin "A") (pinfunction "A_A") (pintype "passive"))
      (node (ref "LED50") (pin "C") (pinfunction "C_C") (pintype "passive"))
    )
    (net (code "50") (name "Net-(LED49-PadC)") (class "Default")
      (node (ref "LED49") (pin "C") (pinfunction "C_C") (pintype "passive"))
      (node (ref "LED50") (pin "A") (pinfunction "A_A") (pintype "passive"))
    )
    (net (code "51") (name "Net-(LED51-PadA)") (class "Default")
      (node (ref "LED51") (pin "A") (pinfunction "A_A") (pintype "passive"))
      (node (ref "LED52") (pin "C") (pinfunction "C_C") (pintype "passive"))
    )
    (net (code "52") (name "Net-(LED51-PadC)") (class "Default")
      (node (ref "LED51") (pin "C") (pinfunction "C_C") (pintype "passive"))
      (node (ref "LED52") (pin "A") (pinfunction "A_A") (pintype "passive"))
    )
    (net (code "53") (name "Net-(LED53-PadA)") (class "Default")
      (node (ref "LED53") (pin "A") (pinfunction "A_A") (pintype "passive"))
      (node (ref "LED54") (pin "C") (pinfunction "C_C") (pintype "passive"))
    )
    (net (code "54") (name "Net-(LED53-PadC)") (class "Default")
      (node (ref "LED53") (pin "C") (pinfunction "C_C") (pintype "passive"))
      (node (ref "LED54") (pin "A") (pinfunction "A_A") (pintype "passive"))
    )
    (net (code "55") (name "Net-(LED55-PadA)") (class "Default")
      (node (ref "LED55") (pin "A") (pinfunction "A_A") (pintype "passive"))
      (node (ref "LED56") (pin "C") (pinfunction "C_C") (pintype "passive"))
    )
    (net (code "56") (name "Net-(LED55-PadC)") (class "Default")
      (node (ref "LED55") (pin "C") (pinfunction "C_C") (pintype "passive"))
      (node (ref "LED56") (pin "A") (pinfunction "A_A") (pintype "passive"))
    )
    (net (code "57") (name "Net-(LED57-PadA)") (class "Default")
      (node (ref "LED57") (pin "A") (pinfunction "A_A") (pintype "passive"))
      (node (ref "LED58") (pin "C") (pinfunction "C_C") (pintype "passive"))
    )
    (net (code "58") (name "Net-(LED57-PadC)") (class "Default")
      (node (ref "LED57") (pin "C") (pinfunction "C_C") (pintype "passive"))
      (node (ref "LED58") (pin "A") (pinfunction "A_A") (pintype "passive"))
    )
    (net (code "59") (name "Net-(LED59-PadA)") (class "Default")
      (node (ref "LED59") (pin "A") (pinfunction "A_A") (pintype "passive"))
      (node (ref "LED60") (pin "C") (pinfunction "C_C") (pintype "passive"))
    )
    (net (code "60") (name "Net-(LED59-PadC)") (class "Default")
      (node (ref "LED59") (pin "C") (pinfunction "C_C") (pintype "passive"))
      (node (ref "LED60") (pin "A") (pinfunction "A_A") (pintype "passive"))
    )
    (net (code "61") (name "Net-(LED62-PadA)") (class "Default")
      (node (ref "LED62") (pin "A") (pinfunction "A_A") (pintype "passive"))
      (node (ref "LED63") (pin "C") (pinfunction "C_C") (pintype "passive"))
    )
    (net (code "62") (name "Net-(LED62-PadC)") (class "Default")
      (node (ref "LED62") (pin "C") (pinfunction "C_C") (pintype "passive"))
      (node (ref "LED63") (pin "A") (pinfunction "A_A") (pintype "passive"))
    )
    (net (code "63") (name "Net-(LED64-PadA)") (class "Default")
      (node (ref "LED64") (pin "A") (pinfunction "A_A") (pintype "passive"))
      (node (ref "LED65") (pin "C") (pinfunction "C_C") (pintype "passive"))
    )
    (net (code "64") (name "Net-(LED64-PadC)") (class "Default")
      (node (ref "LED64") (pin "C") (pinfunction "C_C") (pintype "passive"))
      (node (ref "LED65") (pin "A") (pinfunction "A_A") (pintype "passive"))
    )
    (net (code "65") (name "Net-(LED66-PadA)") (class "Default")
      (node (ref "LED66") (pin "A") (pinfunction "A_A") (pintype "passive"))
      (node (ref "LED67") (pin "C") (pinfunction "C_C") (pintype "passive"))
    )
    (net (code "66") (name "Net-(LED66-PadC)") (class "Default")
      (node (ref "LED66") (pin "C") (pinfunction "C_C") (pintype "passive"))
      (node (ref "LED67") (pin "A") (pinfunction "A_A") (pintype "passive"))
    )
    (net (code "67") (name "Net-(LED68-PadA)") (class "Default")
      (node (ref "LED68") (pin "A") (pinfunction "A_A") (pintype "passive"))
      (node (ref "LED69") (pin "C") (pinfunction "C_C") (pintype "passive"))
    )
    (net (code "68") (name "Net-(LED68-PadC)") (class "Default")
      (node (ref "LED68") (pin "C") (pinfunction "C_C") (pintype "passive"))
      (node (ref "LED69") (pin "A") (pinfunction "A_A") (pintype "passive"))
    )
    (net (code "69") (name "Net-(LED70-PadA)") (class "Default")
      (node (ref "LED70") (pin "A") (pinfunction "A_A") (pintype "passive"))
      (node (ref "LED71") (pin "C") (pinfunction "C_C") (pintype "passive"))
    )
    (net (code "70") (name "Net-(LED70-PadC)") (class "Default")
      (node (ref "LED70") (pin "C") (pinfunction "C_C") (pintype "passive"))
      (node (ref "LED71") (pin "A") (pinfunction "A_A") (pintype "passive"))
    )
    (net (code "71") (name "Net-(LED72-PadA)") (class "Default")
      (node (ref "LED72") (pin "A") (pinfunction "A_A") (pintype "passive"))
      (node (ref "LED73") (pin "C") (pinfunction "C_C") (pintype "passive"))
    )
    (net (code "72") (name "Net-(LED72-PadC)") (class "Default")
      (node (ref "LED72") (pin "C") (pinfunction "C_C") (pintype "passive"))
      (node (ref "LED73") (pin "A") (pinfunction "A_A") (pintype "passive"))
    )
    (net (code "73") (name "Net-(LED74-PadA)") (class "Default")
      (node (ref "LED74") (pin "A") (pinfunction "A_A") (pintype "passive"))
      (node (ref "LED75") (pin "C") (pinfunction "C_C") (pintype "passive"))
    )
    (net (code "74") (name "Net-(LED74-PadC)") (class "Default")
      (node (ref "LED74") (pin "C") (pinfunction "C_C") (pintype "passive"))
      (node (ref "LED75") (pin "A") (pinfunction "A_A") (pintype "passive"))
    )
    (net (code "75") (name "Net-(LED76-PadA)") (class "Default")
      (node (ref "LED76") (pin "A") (pinfunction "A_A") (pintype "passive"))
      (node (ref "LED77") (pin "C") (pinfunction "C_C") (pintype "passive"))
    )
    (net (code "76") (name "Net-(LED76-PadC)") (class "Default")
      (node (ref "LED76") (pin "C") (pinfunction "C_C") (pintype "passive"))
      (node (ref "LED77") (pin "A") (pinfunction "A_A") (pintype "passive"))
    )
    (net (code "77") (name "Net-(LED78-PadA)") (class "Default")
      (node (ref "LED78") (pin "A") (pinfunction "A_A") (pintype "passive"))
      (node (ref "LED79") (pin "C") (pinfunction "C_C") (pintype "passive"))
    )
    (net (code "78") (name "Net-(LED78-PadC)") (class "Default")
      (node (ref "LED78") (pin "C") (pinfunction "C_C") (pintype "passive"))
      (node (ref "LED79") (pin "A") (pinfunction "A_A") (pintype "passive"))
    )
    (net (code "79") (name "Net-(LED80-PadA)") (class "Default")
      (node (ref "LED80") (pin "A") (pinfunction "A_A") (pintype "passive"))
      (node (ref "LED81") (pin "C") (pinfunction "C_C") (pintype "passive"))
    )
    (net (code "80") (name "Net-(LED80-PadC)") (class "Default")
      (node (ref "LED80") (pin "C") (pinfunction "C_C") (pintype "passive"))
      (node (ref "LED81") (pin "A") (pinfunction "A_A") (pintype "passive"))
    )
    (net (code "81") (name "Net-(LED82-PadA)") (class "Default")
      (node (ref "LED82") (pin "A") (pinfunction "A_A") (pintype "passive"))
      (node (ref "LED83") (pin "C") (pinfunction "C_C") (pintype "passive"))
    )
    (net (code "82") (name "Net-(LED82-PadC)") (class "Default")
      (node (ref "LED82") (pin "C") (pinfunction "C_C") (pintype "passive"))
      (node (ref "LED83") (pin "A") (pinfunction "A_A") (pintype "passive"))
    )
    (net (code "83") (name "Net-(LED84-PadA)") (class "Default")
      (node (ref "LED84") (pin "A") (pinfunction "A_A") (pintype "passive"))
      (node (ref "LED85") (pin "C") (pinfunction "C_C") (pintype "passive"))
    )
    (net (code "84") (name "Net-(LED84-PadC)") (class "Default")
      (node (ref "LED84") (pin "C") (pinfunction "C_C") (pintype "passive"))
      (node (ref "LED85") (pin "A") (pinfunction "A_A") (pintype "passive"))
    )
    (net (code "85") (name "Net-(LED86-PadA)") (class "Default")
      (node (ref "LED86") (pin "A") (pinfunction "A_A") (pintype "passive"))
      (node (ref "LED87") (pin "C") (pinfunction "C_C") (pintype "passive"))
    )
    (net (code "86") (name "Net-(LED86-PadC)") (class "Default")
      (node (ref "LED86") (pin "C") (pinfunction "C_C") (pintype "passive"))
      (node (ref "LED87") (pin "A") (pinfunction "A_A") (pintype "passive"))
    )
    (net (code "87") (name "Net-(LED88-PadA)") (class "Default")
      (node (ref "LED88") (pin "A") (pinfunction "A_A") (pintype "passive"))
      (node (ref "LED89") (pin "C") (pinfunction "C_C") (pintype "passive"))
    )
    (net (code "88") (name "Net-(LED88-PadC)") (class "Default")
      (node (ref "LED88") (pin "C") (pinfunction "C_C") (pintype "passive"))
      (node (ref "LED89") (pin "A") (pinfunction "A_A") (pintype "passive"))
    )
    (net (code "89") (name "Net-(LED90-PadA)") (class "Default")
      (node (ref "LED90") (pin "A") (pinfunction "A_A") (pintype "passive"))
      (node (ref "LED91") (pin "C") (pinfunction "C_C") (pintype "passive"))
    )
    (net (code "90") (name "Net-(LED90-PadC)") (class "Default")
      (node (ref "LED90") (pin "C") (pinfunction "C_C") (pintype "passive"))
      (node (ref "LED91") (pin "A") (pinfunction "A_A") (pintype "passive"))
    )
    (net (code "91") (name "Net-(LED92-PadA)") (class "Default")
      (node (ref "LED92") (pin "A") (pinfunction "A_A") (pintype "passive"))
      (node (ref "LED93") (pin "C") (pinfunction "C_C") (pintype "passive"))
    )
    (net (code "92") (name "Net-(LED92-PadC)") (class "Default")
      (node (ref "LED92") (pin "C") (pinfunction "C_C") (pintype "passive"))
      (node (ref "LED93") (pin "A") (pinfunction "A_A") (pintype "passive"))
    )
    (net (code "93") (name "Net-(LED94-PadA)") (class "Default")
      (node (ref "LED94") (pin "A") (pinfunction "A_A") (pintype "passive"))
      (node (ref "LED95") (pin "C") (pinfunction "C_C") (pintype "passive"))
    )
    (net (code "94") (name "Net-(LED94-PadC)") (class "Default")
      (node (ref "LED94") (pin "C") (pinfunction "C_C") (pintype "passive"))
      (node (ref "LED95") (pin "A") (pinfunction "A_A") (pintype "passive"))
    )
    (net (code "95") (name "Net-(LED96-PadA)") (class "Default")
      (node (ref "LED96") (pin "A") (pinfunction "A_A") (pintype "passive"))
      (node (ref "LED97") (pin "C") (pinfunction "C_C") (pintype "passive"))
    )
    (net (code "96") (name "Net-(LED96-PadC)") (class "Default")
      (node (ref "LED96") (pin "C") (pinfunction "C_C") (pintype "passive"))
      (node (ref "LED97") (pin "A") (pinfunction "A_A") (pintype "passive"))
    )
    (net (code "97") (name "Net-(LED98-PadA)") (class "Default")
      (node (ref "LED98") (pin "A") (pinfunction "A_A") (pintype "passive"))
      (node (ref "LED99") (pin "C") (pinfunction "C_C") (pintype "passive"))
    )
    (net (code "98") (name "Net-(LED98-PadC)") (class "Default")
      (node (ref "LED98") (pin "C") (pinfunction "C_C") (pintype "passive"))
      (node (ref "LED99") (pin "A") (pinfunction "A_A") (pintype "passive"))
    )
    (net (code "99") (name "Net-(LED100-PadA)") (class "Default")
      (node (ref "LED100") (pin "A") (pinfunction "A_A") (pintype "passive"))
      (node (ref "LED101") (pin "C") (pinfunction "C_C") (pintype "passive"))
    )
    (net (code "100") (name "Net-(LED100-PadC)") (class "Default")
      (node (ref "LED100") (pin "C") (pinfunction "C_C") (pintype "passive"))
      (node (ref "LED101") (pin "A") (pinfunction "A_A") (pintype "passive"))
    )
    (net (code "101") (name "Net-(LED102-PadA)") (class "Default")
      (node (ref "LED102") (pin "A") (pinfunction "A_A") (pintype "passive"))
      (node (ref "LED103") (pin "C") (pinfunction "C_C") (pintype "passive"))
    )
    (net (code "102") (name "Net-(LED102-PadC)") (class "Default")
      (node (ref "LED102") (pin "C") (pinfunction "C_C") (pintype "passive"))
      (node (ref "LED103") (pin "A") (pinfunction "A_A") (pintype "passive"))
    )
    (net (code "103") (name "Net-(LED104-PadA)") (class "Default")
      (node (ref "LED104") (pin "A") (pinfunction "A_A") (pintype "passive"))
      (node (ref "LED105") (pin "C") (pinfunction "C_C") (pintype "passive"))
    )
    (net (code "104") (name "Net-(LED104-PadC)") (class "Default")
      (node (ref "LED104") (pin "C") (pinfunction "C_C") (pintype "passive"))
      (node (ref "LED105") (pin "A") (pinfunction "A_A") (pintype "passive"))
    )
    (net (code "105") (name "Net-(LED106-PadA)") (class "Default")
      (node (ref "LED106") (pin "A") (pinfunction "A_A") (pintype "passive"))
      (node (ref "LED107") (pin "C") (pinfunction "C_C") (pintype "passive"))
    )
    (net (code "106") (name "Net-(LED106-PadC)") (class "Default")
      (node (ref "LED106") (pin "C") (pinfunction "C_C") (pintype "passive"))
      (node (ref "LED107") (pin "A") (pinfunction "A_A") (pintype "passive"))
    )
    (net (code "107") (name "Net-(LED108-PadA)") (class "Default")
      (node (ref "LED108") (pin "A") (pinfunction "A_A") (pintype "passive"))
      (node (ref "LED109") (pin "C") (pinfunction "C_C") (pintype "passive"))
    )
    (net (code "108") (name "Net-(LED108-PadC)") (class "Default")
      (node (ref "LED108") (pin "C") (pinfunction "C_C") (pintype "passive"))
      (node (ref "LED109") (pin "A") (pinfunction "A_A") (pintype "passive"))
    )
    (net (code "109") (name "Net-(LED110-PadA)") (class "Default")
      (node (ref "LED110") (pin "A") (pinfunction "A_A") (pintype "passive"))
      (node (ref "LED111") (pin "C") (pinfunction "C_C") (pintype "passive"))
    )
    (net (code "110") (name "Net-(LED110-PadC)") (class "Default")
      (node (ref "LED110") (pin "C") (pinfunction "C_C") (pintype "passive"))
      (node (ref "LED111") (pin "A") (pinfunction "A_A") (pintype "passive"))
    )
    (net (code "111") (name "Net-(LED112-PadA)") (class "Default")
      (node (ref "LED112") (pin "A") (pinfunction "A_A") (pintype "passive"))
      (node (ref "LED113") (pin "C") (pinfunction "C_C") (pintype "passive"))
    )
    (net (code "112") (name "Net-(LED112-PadC)") (class "Default")
      (node (ref "LED112") (pin "C") (pinfunction "C_C") (pintype "passive"))
      (node (ref "LED113") (pin "A") (pinfunction "A_A") (pintype "passive"))
    )
    (net (code "113") (name "Net-(LED114-PadA)") (class "Default")
      (node (ref "LED114") (pin "A") (pinfunction "A_A") (pintype "passive"))
      (node (ref "LED115") (pin "C") (pinfunction "C_C") (pintype "passive"))
    )
    (net (code "114") (name "Net-(LED114-PadC)") (class "Default")
      (node (ref "LED114") (pin "C") (pinfunction "C_C") (pintype "passive"))
      (node (ref "LED115") (pin "A") (pinfunction "A_A") (pintype "passive"))
    )
    (net (code "115") (name "Net-(LED116-PadA)") (class "Default")
      (node (ref "LED116") (pin "A") (pinfunction "A_A") (pintype "passive"))
      (node (ref "LED117") (pin "C") (pinfunction "C_C") (pintype "passive"))
    )
    (net (code "116") (name "Net-(LED116-PadC)") (class "Default")
      (node (ref "LED116") (pin "C") (pinfunction "C_C") (pintype "passive"))
      (node (ref "LED117") (pin "A") (pinfunction "A_A") (pintype "passive"))
    )
    (net (code "117") (name "Net-(LED118-PadA)") (class "Default")
      (node (ref "LED118") (pin "A") (pinfunction "A_A") (pintype "passive"))
      (node (ref "LED119") (pin "C") (pinfunction "C_C") (pintype "passive"))
    )
    (net (code "118") (name "Net-(LED118-PadC)") (class "Default")
      (node (ref "LED118") (pin "C") (pinfunction "C_C") (pintype "passive"))
      (node (ref "LED119") (pin "A") (pinfunction "A_A") (pintype "passive"))
    )
    (net (code "119") (name "Net-(LED120-PadA)") (class "Default")
      (node (ref "LED120") (pin "A") (pinfunction "A_A") (pintype "passive"))
      (node (ref "LED61") (pin "C") (pinfunction "C_C") (pintype "passive"))
    )
    (net (code "120") (name "Net-(LED120-PadC)") (class "Default")
      (node (ref "LED120") (pin "C") (pinfunction "C_C") (pintype "passive"))
      (node (ref "LED61") (pin "A") (pinfunction "A_A") (pintype "passive"))
    )
    (net (code "121") (name "Net-(LED121-PadA)") (class "Default")
      (node (ref "LED121") (pin "A") (pinfunction "A_A") (pintype "passive"))
      (node (ref "LED122") (pin "C") (pinfunction "C_C") (pintype "passive"))
    )
    (net (code "122") (name "Net-(LED121-PadC)") (class "Default")
      (node (ref "LED121") (pin "C") (pinfunction "C_C") (pintype "passive"))
      (node (ref "LED122") (pin "A") (pinfunction "A_A") (pintype "passive"))
    )
    (net (code "123") (name "Net-(LED123-PadA)") (class "Default")
      (node (ref "LED123") (pin "A") (pinfunction "A_A") (pintype "passive"))
      (node (ref "LED124") (pin "C") (pinfunction "C_C") (pintype "passive"))
    )
    (net (code "124") (name "Net-(LED123-PadC)") (class "Default")
      (node (ref "LED123") (pin "C") (pinfunction "C_C") (pintype "passive"))
      (node (ref "LED124") (pin "A") (pinfunction "A_A") (pintype "passive"))
    )
    (net (code "125") (name "Net-(LED125-PadA)") (class "Default")
      (node (ref "LED125") (pin "A") (pinfunction "A_A") (pintype "passive"))
      (node (ref "LED126") (pin "C") (pinfunction "C_C") (pintype "passive"))
    )
    (net (code "126") (name "Net-(LED125-PadC)") (class "Default")
      (node (ref "LED125") (pin "C") (pinfunction "C_C") (pintype "passive"))
      (node (ref "LED126") (pin "A") (pinfunction "A_A") (pintype "passive"))
    )
    (net (code "127") (name "Net-(LED127-PadA)") (class "Default")
      (node (ref "LED127") (pin "A") (pinfunction "A_A") (pintype "passive"))
      (node (ref "LED128") (pin "C") (pinfunction "C_C") (pintype "passive"))
    )
    (net (code "128") (name "Net-(LED127-PadC)") (class "Default")
      (node (ref "LED127") (pin "C") (pinfunction "C_C") (pintype "passive"))
      (node (ref "LED128") (pin "A") (pinfunction "A_A") (pintype "passive"))
    )
    (net (code "129") (name "Net-(LED129-PadA)") (class "Default")
      (node (ref "LED129") (pin "A") (pinfunction "A_A") (pintype "passive"))
      (node (ref "LED130") (pin "C") (pinfunction "C_C") (pintype "passive"))
    )
    (net (code "130") (name "Net-(LED129-PadC)") (class "Default")
      (node (ref "LED129") (pin "C") (pinfunction "C_C") (pintype "passive"))
      (node (ref "LED130") (pin "A") (pinfunction "A_A") (pintype "passive"))
    )
    (net (code "131") (name "Net-(LED131-PadA)") (class "Default")
      (node (ref "LED131") (pin "A") (pinfunction "A_A") (pintype "passive"))
      (node (ref "LED132") (pin "C") (pinfunction "C_C") (pintype "passive"))
    )
    (net (code "132") (name "Net-(LED131-PadC)") (class "Default")
      (node (ref "LED131") (pin "C") (pinfunction "C_C") (pintype "passive"))
      (node (ref "LED132") (pin "A") (pinfunction "A_A") (pintype "passive"))
    )
    (net (code "133") (name "Net-(LED133-PadA)") (class "Default")
      (node (ref "LED133") (pin "A") (pinfunction "A_A") (pintype "passive"))
      (node (ref "LED134") (pin "C") (pinfunction "C_C") (pintype "passive"))
    )
    (net (code "134") (name "Net-(LED133-PadC)") (class "Default")
      (node (ref "LED133") (pin "C") (pinfunction "C_C") (pintype "passive"))
      (node (ref "LED134") (pin "A") (pinfunction "A_A") (pintype "passive"))
    )
    (net (code "135") (name "Net-(LED135-PadA)") (class "Default")
      (node (ref "LED135") (pin "A") (pinfunction "A_A") (pintype "passive"))
      (node (ref "LED136") (pin "C") (pinfunction "C_C") (pintype "passive"))
    )
    (net (code "136") (name "Net-(LED135-PadC)") (class "Default")
      (node (ref "LED135") (pin "C") (pinfunction "C_C") (pintype "passive"))
      (node (ref "LED136") (pin "A") (pinfunction "A_A") (pintype "passive"))
    )
    (net (code "137") (name "Net-(LED137-PadA)") (class "Default")
      (node (ref "LED137") (pin "A") (pinfunction "A_A") (pintype "passive"))
      (node (ref "LED138") (pin "C") (pinfunction "C_C") (pintype "passive"))
    )
    (net (code "138") (name "Net-(LED137-PadC)") (class "Default")
      (node (ref "LED137") (pin "C") (pinfunction "C_C") (pintype "passive"))
      (node (ref "LED138") (pin "A") (pinfunction "A_A") (pintype "passive"))
    )
    (net (code "139") (name "Net-(LED139-PadA)") (class "Default")
      (node (ref "LED139") (pin "A") (pinfunction "A_A") (pintype "passive"))
      (node (ref "LED140") (pin "C") (pinfunction "C_C") (pintype "passive"))
    )
    (net (code "140") (name "Net-(LED139-PadC)") (class "Default")
      (node (ref "LED139") (pin "C") (pinfunction "C_C") (pintype "passive"))
      (node (ref "LED140") (pin "A") (pinfunction "A_A") (pintype "passive"))
    )
    (net (code "141") (name "Net-(LED141-PadA)") (class "Default")
      (node (ref "LED141") (pin "A") (pinfunction "A_A") (pintype "passive"))
      (node (ref "LED142") (pin "C") (pinfunction "C_C") (pintype "passive"))
    )
    (net (code "142") (name "Net-(LED141-PadC)") (class "Default")
      (node (ref "LED141") (pin "C") (pinfunction "C_C") (pintype "passive"))
      (node (ref "LED142") (pin "A") (pinfunction "A_A") (pintype "passive"))
    )
    (net (code "143") (name "Net-(LED143-PadA)") (class "Default")
      (node (ref "LED143") (pin "A") (pinfunction "A_A") (pintype "passive"))
      (node (ref "LED144") (pin "C") (pinfunction "C_C") (pintype "passive"))
    )
    (net (code "144") (name "Net-(LED143-PadC)") (class "Default")
      (node (ref "LED143") (pin "C") (pinfunction "C_C") (pintype "passive"))
      (node (ref "LED144") (pin "A") (pinfunction "A_A") (pintype "passive"))
    )
    (net (code "145") (name "Net-(LED145-PadA)") (class "Default")
      (node (ref "LED145") (pin "A") (pinfunction "A_A") (pintype "passive"))
      (node (ref "LED146") (pin "C") (pinfunction "C_C") (pintype "passive"))
    )
    (net (code "146") (name "Net-(LED145-PadC)") (class "Default")
      (node (ref "LED145") (pin "C") (pinfunction "C_C") (pintype "passive"))
      (node (ref "LED146") (pin "A") (pinfunction "A_A") (pintype "passive"))
    )
    (net (code "147") (name "Net-(LED147-PadA)") (class "Default")
      (node (ref "LED147") (pin "A") (pinfunction "A_A") (pintype "passive"))
      (node (ref "LED148") (pin "C") (pinfunction "C_C") (pintype "passive"))
    )
    (net (code "148") (name "Net-(LED147-PadC)") (class "Default")
      (node (ref "LED147") (pin "C") (pinfunction "C_C") (pintype "passive"))
      (node (ref "LED148") (pin "A") (pinfunction "A_A") (pintype "passive"))
    )
    (net (code "149") (name "Net-(LED149-PadA)") (class "Default")
      (node (ref "LED149") (pin "A") (pinfunction "A_A") (pintype "passive"))
      (node (ref "LED150") (pin "C") (pinfunction "C_C") (pintype "passive"))
    )
    (net (code "150") (name "Net-(LED149-PadC)") (class "Default")
      (node (ref "LED149") (pin "C") (pinfunction "C_C") (pintype "passive"))
      (node (ref "LED150") (pin "A") (pinfunction "A_A") (pintype "passive"))
    )
    (net (code "151") (name "Net-(LED151-PadA)") (class "Default")
      (node (ref "LED151") (pin "A") (pinfunction "A_A") (pintype "passive"))
      (node (ref "LED152") (pin "C") (pinfunction "C_C") (pintype "passive"))
    )
    (net (code "152") (name "Net-(LED151-PadC)") (class "Default")
      (node (ref "LED151") (pin "C") (pinfunction "C_C") (pintype "passive"))
      (node (ref "LED152") (pin "A") (pinfunction "A_A") (pintype "passive"))
    )
    (net (code "153") (name "Net-(LED153-PadA)") (class "Default")
      (node (ref "LED153") (pin "A") (pinfunction "A_A") (pintype "passive"))
      (node (ref "LED154") (pin "C") (pinfunction "C_C") (pintype "passive"))
    )
    (net (code "154") (name "Net-(LED153-PadC)") (class "Default")
      (node (ref "LED153") (pin "C") (pinfunction "C_C") (pintype "passive"))
      (node (ref "LED154") (pin "A") (pinfunction "A_A") (pintype "passive"))
    )
    (net (code "155") (name "Net-(LED155-PadA)") (class "Default")
      (node (ref "LED155") (pin "A") (pinfunction "A_A") (pintype "passive"))
      (node (ref "LED156") (pin "C") (pinfunction "C_C") (pintype "passive"))
    )
    (net (code "156") (name "Net-(LED155-PadC)") (class "Default")
      (node (ref "LED155") (pin "C") (pinfunction "C_C") (pintype "passive"))
      (node (ref "LED156") (pin "A") (pinfunction "A_A") (pintype "passive"))
    )
    (net (code "157") (name "Net-(LED157-PadA)") (class "Default")
      (node (ref "LED157") (pin "A") (pinfunction "A_A") (pintype "passive"))
      (node (ref "LED158") (pin "C") (pinfunction "C_C") (pintype "passive"))
    )
    (net (code "158") (name "Net-(LED157-PadC)") (class "Default")
      (node (ref "LED157") (pin "C") (pinfunction "C_C") (pintype "passive"))
      (node (ref "LED158") (pin "A") (pinfunction "A_A") (pintype "passive"))
    )
    (net (code "159") (name "Net-(LED159-PadA)") (class "Default")
      (node (ref "LED159") (pin "A") (pinfunction "A_A") (pintype "passive"))
      (node (ref "LED160") (pin "C") (pinfunction "C_C") (pintype "passive"))
    )
    (net (code "160") (name "Net-(LED159-PadC)") (class "Default")
      (node (ref "LED159") (pin "C") (pinfunction "C_C") (pintype "passive"))
      (node (ref "LED160") (pin "A") (pinfunction "A_A") (pintype "passive"))
    )
    (net (code "161") (name "Net-(LED161-PadA)") (class "Default")
      (node (ref "LED161") (pin "A") (pinfunction "A_A") (pintype "passive"))
      (node (ref "LED162") (pin "C") (pinfunction "C_C") (pintype "passive"))
    )
    (net (code "162") (name "Net-(LED161-PadC)") (class "Default")
      (node (ref "LED161") (pin "C") (pinfunction "C_C") (pintype "passive"))
      (node (ref "LED162") (pin "A") (pinfunction "A_A") (pintype "passive"))
    )
    (net (code "163") (name "Net-(LED163-PadA)") (class "Default")
      (node (ref "LED163") (pin "A") (pinfunction "A_A") (pintype "passive"))
      (node (ref "LED164") (pin "C") (pinfunction "C_C") (pintype "passive"))
    )
    (net (code "164") (name "Net-(LED163-PadC)") (class "Default")
      (node (ref "LED163") (pin "C") (pinfunction "C_C") (pintype "passive"))
      (node (ref "LED164") (pin "A") (pinfunction "A_A") (pintype "passive"))
    )
    (net (code "165") (name "Net-(LED165-PadA)") (class "Default")
      (node (ref "LED165") (pin "A") (pinfunction "A_A") (pintype "passive"))
      (node (ref "LED166") (pin "C") (pinfunction "C_C") (pintype "passive"))
    )
    (net (code "166") (name "Net-(LED165-PadC)") (class "Default")
      (node (ref "LED165") (pin "C") (pinfunction "C_C") (pintype "passive"))
      (node (ref "LED166") (pin "A") (pinfunction "A_A") (pintype "passive"))
    )
    (net (code "167") (name "Net-(LED167-PadA)") (class "Default")
      (node (ref "LED167") (pin "A") (pinfunction "A_A") (pintype "passive"))
      (node (ref "LED168") (pin "C") (pinfunction "C_C") (pintype "passive"))
    )
    (net (code "168") (name "Net-(LED167-PadC)") (class "Default")
      (node (ref "LED167") (pin "C") (pinfunction "C_C") (pintype "passive"))
      (node (ref "LED168") (pin "A") (pinfunction "A_A") (pintype "passive"))
    )
    (net (code "169") (name "Net-(LED169-PadA)") (class "Default")
      (node (ref "LED169") (pin "A") (pinfunction "A_A") (pintype "passive"))
      (node (ref "LED170") (pin "C") (pinfunction "C_C") (pintype "passive"))
    )
    (net (code "170") (name "Net-(LED169-PadC)") (class "Default")
      (node (ref "LED169") (pin "C") (pinfunction "C_C") (pintype "passive"))
      (node (ref "LED170") (pin "A") (pinfunction "A_A") (pintype "passive"))
    )
    (net (code "171") (name "Net-(LED171-PadA)") (class "Default")
      (node (ref "LED171") (pin "A") (pinfunction "A_A") (pintype "passive"))
      (node (ref "LED172") (pin "C") (pinfunction "C_C") (pintype "passive"))
    )
    (net (code "172") (name "Net-(LED171-PadC)") (class "Default")
      (node (ref "LED171") (pin "C") (pinfunction "C_C") (pintype "passive"))
      (node (ref "LED172") (pin "A") (pinfunction "A_A") (pintype "passive"))
    )
    (net (code "173") (name "Net-(LED173-PadA)") (class "Default")
      (node (ref "LED173") (pin "A") (pinfunction "A_A") (pintype "passive"))
      (node (ref "LED174") (pin "C") (pinfunction "C_C") (pintype "passive"))
    )
    (net (code "174") (name "Net-(LED173-PadC)") (class "Default")
      (node (ref "LED173") (pin "C") (pinfunction "C_C") (pintype "passive"))
      (node (ref "LED174") (pin "A") (pinfunction "A_A") (pintype "passive"))
    )
    (net (code "175") (name "Net-(LED175-PadA)") (class "Default")
      (node (ref "LED175") (pin "A") (pinfunction "A_A") (pintype "passive"))
      (node (ref "LED176") (pin "C") (pinfunction "C_C") (pintype "passive"))
    )
    (net (code "176") (name "Net-(LED175-PadC)") (class "Default")
      (node (ref "LED175") (pin "C") (pinfunction "C_C") (pintype "passive"))
      (node (ref "LED176") (pin "A") (pinfunction "A_A") (pintype "passive"))
    )
    (net (code "177") (name "Net-(LED177-PadA)") (class "Default")
      (node (ref "LED177") (pin "A") (pinfunction "A_A") (pintype "passive"))
      (node (ref "LED178") (pin "C") (pinfunction "C_C") (pintype "passive"))
    )
    (net (code "178") (name "Net-(LED177-PadC)") (class "Default")
      (node (ref "LED177") (pin "C") (pinfunction "C_C") (pintype "passive"))
      (node (ref "LED178") (pin "A") (pinfunction "A_A") (pintype "passive"))
    )
    (net (code "179") (name "Net-(LED179-PadA)") (class "Default")
      (node (ref "LED179") (pin "A") (pinfunction "A_A") (pintype "passive"))
      (node (ref "LED180") (pin "C") (pinfunction "C_C") (pintype "passive"))
    )
    (net (code "180") (name "Net-(LED179-PadC)") (class "Default")
      (node (ref "LED179") (pin "C") (pinfunction "C_C") (pintype "passive"))
      (node (ref "LED180") (pin "A") (pinfunction "A_A") (pintype "passive"))
    )
  )
)
